# HV_Module.net
KiCad netlist of a schematic drawn in Altium Designer
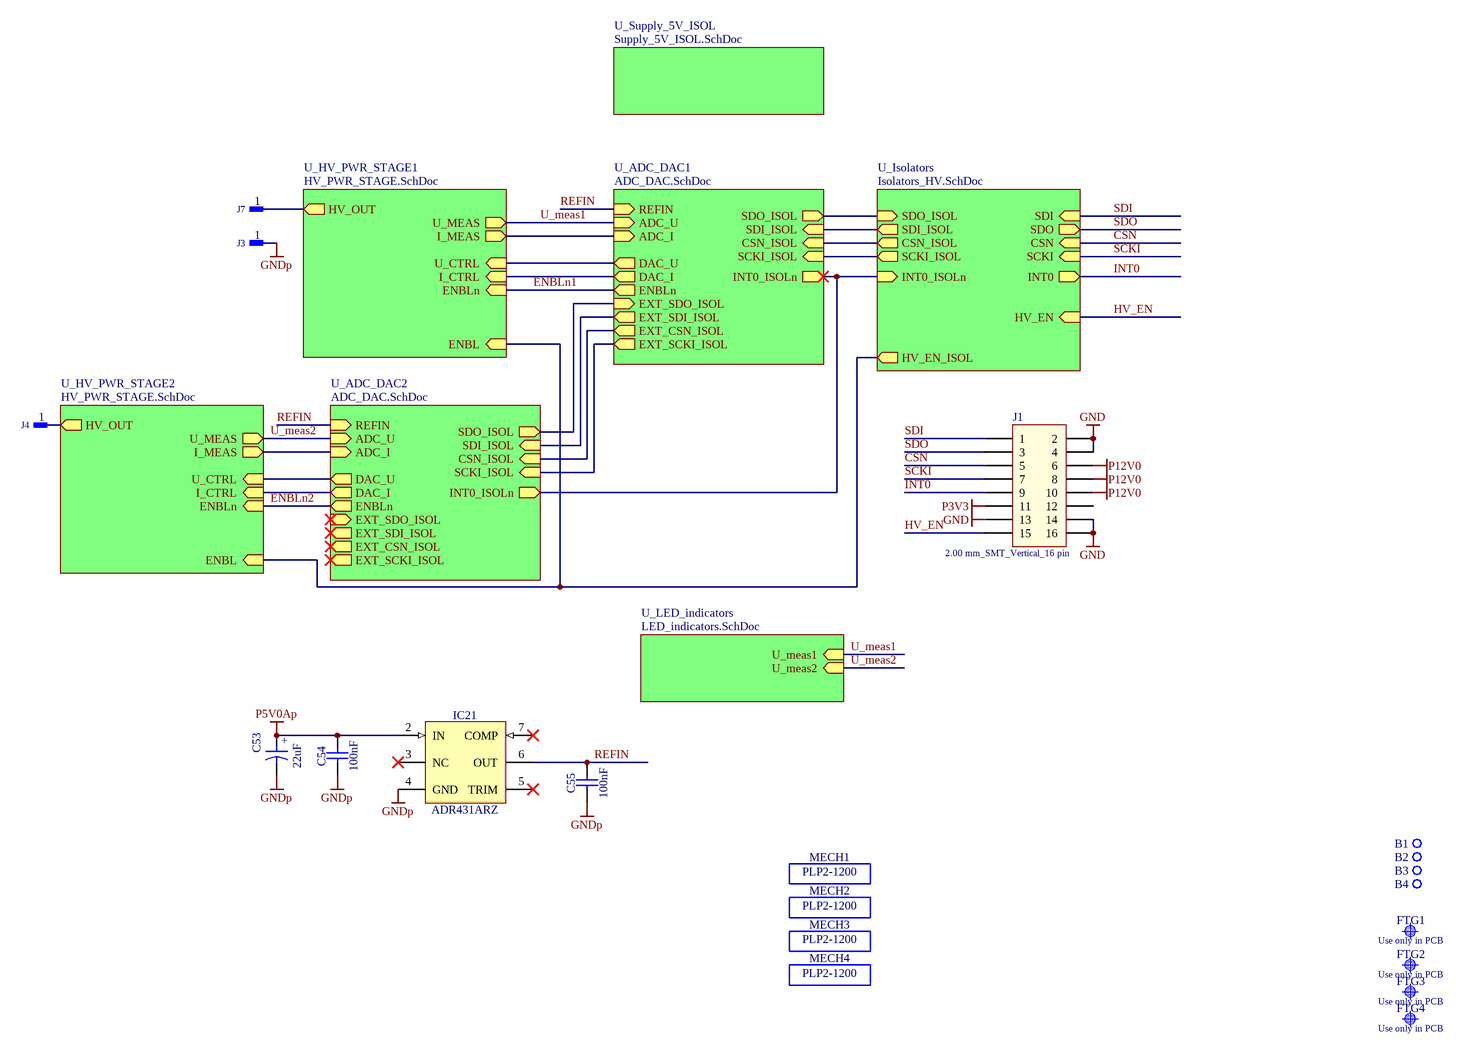
[diagram p0: HV_Module.schdoc]

(export (version "E")
  (design (tool "Eeschema 10.0.6"))
  (components
    (comp (ref "B1")
      (value "Plated Hole")
      (footprint "MTG270_500")
      (description "Single Terminal Socket")
      (fields (field (name "PART NUMBER") "PLATED_HOLE2.7_PAD5.0") (field (name "AUTHOR") "CERN DEM JMW"))
      (libsource (lib "Eletro-mechanical") (part "Single Terminal Socket"))
    )
    (comp (ref "B2")
      (value "Plated Hole")
      (footprint "MTG270_500")
      (description "Single Terminal Socket")
      (fields (field (name "PART NUMBER") "PLATED_HOLE2.7_PAD5.0") (field (name "AUTHOR") "CERN DEM JMW"))
      (libsource (lib "Eletro-mechanical") (part "Single Terminal Socket"))
    )
    (comp (ref "B3")
      (value "Plated Hole")
      (footprint "MTG270_500")
      (description "Single Terminal Socket")
      (fields (field (name "PART NUMBER") "PLATED_HOLE2.7_PAD5.0") (field (name "AUTHOR") "CERN DEM JMW"))
      (libsource (lib "Eletro-mechanical") (part "Single Terminal Socket"))
    )
    (comp (ref "B4")
      (value "Plated Hole")
      (footprint "MTG270_500")
      (description "Single Terminal Socket")
      (fields (field (name "PART NUMBER") "PLATED_HOLE2.7_PAD5.0") (field (name "AUTHOR") "CERN DEM JMW"))
      (libsource (lib "Eletro-mechanical") (part "Single Terminal Socket"))
    )
    (comp (ref "C53")
      (value "22uF")
      (footprint "CAPMP3528X210N")
      (description "Polarised capacitor")
      (fields
        (field (name "PART NUMBER") "CTE3528-21_22UF_20V_10%")
        (field (name "VOLTAGE") "20V")
        (field (name "AUTHOR") "CERN DEM JLC")
      )
      (libsource (lib "Capacitors") (part "Capacitor - polarized"))
    )
    (comp (ref "C54")
      (value "100nF")
      (footprint "CAPC1005X55N")
      (description "Non-polarised capacitor")
      (fields
        (field (name "PART NUMBER") "CC0402_100NF_16V_10%_X7R")
        (field (name "VOLTAGE") "16V")
        (field (name "AUTHOR") "CERN DEM JLC")
      )
      (libsource (lib "Capacitors") (part "Capacitor - non polarized"))
    )
    (comp (ref "C55")
      (value "100nF")
      (footprint "CAPC1005X55N")
      (description "Non-polarised capacitor")
      (fields
        (field (name "PART NUMBER") "CC0402_100NF_16V_10%_X7R")
        (field (name "VOLTAGE") "16V")
        (field (name "AUTHOR") "CERN DEM JLC")
      )
      (libsource (lib "Capacitors") (part "Capacitor - non polarized"))
    )
    (comp (ref "FTG1")
      (value "Use only in PCB")
      (footprint "FIDUCIAL_TOP_C100-200")
      (description "Fiducial Target")
      (fields (field (name "PART NUMBER") "FIDUCIAL_TARGET_C100-200") (field (name "AUTHOR") "CERN DEM JLC"))
      (libsource (lib "Eletro-mechanical") (part "Fiducial Target"))
    )
    (comp (ref "FTG2")
      (value "Use only in PCB")
      (footprint "FIDUCIAL_TOP_S100-200")
      (description "Fiducial Target")
      (fields (field (name "PART NUMBER") "FIDUCIAL_TARGET_S100-200") (field (name "AUTHOR") "CERN DEM JLC"))
      (libsource (lib "Eletro-mechanical") (part "Fiducial Target"))
    )
    (comp (ref "FTG3")
      (value "Use only in PCB")
      (footprint "FIDUCIAL_TOP_S100-200")
      (description "Fiducial Target")
      (fields (field (name "PART NUMBER") "FIDUCIAL_TARGET_S100-200") (field (name "AUTHOR") "CERN DEM JLC"))
      (libsource (lib "Eletro-mechanical") (part "Fiducial Target"))
    )
    (comp (ref "FTG4")
      (value "Use only in PCB")
      (footprint "FIDUCIAL_TOP_S100-200")
      (description "Fiducial Target")
      (fields (field (name "PART NUMBER") "FIDUCIAL_TARGET_S100-200") (field (name "AUTHOR") "CERN DEM JLC"))
      (libsource (lib "Eletro-mechanical") (part "Fiducial Target"))
    )
    (comp (ref "IC21")
      (value "ADR431ARZ")
      (footprint "SOIC127P600X175-8N")
      (fields (field (name "MANUFACTURER") "ANALOG DEVICES") (field (name "AUTHOR") "CERN DEM JLC"))
      (libsource (lib "ICs And Semiconductors") (part "ADR431"))
    )
    (comp (ref "J1")
      (value "2.00 mm_SMT_Vertical_16 pin")
      (footprint "62131621821")
      (description "Socket Header WR-PHD, Pitch 2.00 mm, SMT, Vertical, dual row, 16 pin")
      (fields (field (name "PART NUMBER") "62131621821") (field (name "PUBLISHER") "Wurth Elektronik"))
      (libsource (lib "ALTIUM-PHD_2_0_SMT_DUAL_SOCKET_HEADER_LOW_PROFILE_REEL_6213XX21821-rev18a") (part "62131621821"))
    )
    (comp (ref "J3")
      (value "SMD Pad")
      (footprint "R400X300")
      (description "Single SMD Pad")
      (fields (field (name "PART NUMBER") "SMD_PAD_4X3MM") (field (name "AUTHOR") "CERN DEM JLC"))
      (libsource (lib "Eletro-mechanical") (part "Single SMD Pad"))
    )
    (comp (ref "J4")
      (value "SMD Pad")
      (footprint "R400X300")
      (description "Single SMD Pad")
      (fields (field (name "PART NUMBER") "SMD_PAD_4X3MM") (field (name "AUTHOR") "CERN DEM JLC"))
      (libsource (lib "Eletro-mechanical") (part "Single SMD Pad"))
    )
    (comp (ref "J7")
      (value "SMD Pad")
      (footprint "R400X300")
      (description "Single SMD Pad")
      (fields (field (name "PART NUMBER") "SMD_PAD_4X3MM") (field (name "AUTHOR") "CERN DEM JLC"))
      (libsource (lib "Eletro-mechanical") (part "Single SMD Pad"))
    )
    (comp (ref "MECH1")
      (value "PLP2-1200")
      (footprint "GENERIC_MECH")
      (description "Lightguide")
      (fields (field (name "MANUFACTURER") "BIvar") (field (name "AUTHOR") "GK"))
      (libsource (lib "Mechanical") (part "Generic_mechanical"))
    )
    (comp (ref "MECH2")
      (value "PLP2-1200")
      (footprint "GENERIC_MECH")
      (description "Lightguide")
      (fields (field (name "MANUFACTURER") "BIvar") (field (name "AUTHOR") "GK"))
      (libsource (lib "Mechanical") (part "Generic_mechanical"))
    )
    (comp (ref "MECH3")
      (value "PLP2-1200")
      (footprint "GENERIC_MECH")
      (description "Lightguide")
      (fields (field (name "MANUFACTURER") "BIvar") (field (name "AUTHOR") "GK"))
      (libsource (lib "Mechanical") (part "Generic_mechanical"))
    )
    (comp (ref "MECH4")
      (value "PLP2-1200")
      (footprint "GENERIC_MECH")
      (description "Lightguide")
      (fields (field (name "MANUFACTURER") "BIvar") (field (name "AUTHOR") "GK"))
      (libsource (lib "Mechanical") (part "Generic_mechanical"))
    )
  )
  (nets
    (net (code "1") (name "/CSN") (class "Default")
      (node (ref "J1") (pin "5") (pinfunction "5_5") (pintype "passive"))
    )
    (net (code "16") (name "/HV_EN") (class "Default")
      (node (ref "J1") (pin "15") (pinfunction "15_15") (pintype "passive"))
    )
    (net (code "18") (name "/HV_OUT") (class "Default")
      (node (ref "J7") (pin "1") (pinfunction "1_1") (pintype "bidirectional"))
    )
    (net (code "19") (name "/HV_OUT_1") (class "Default")
      (node (ref "J4") (pin "1") (pinfunction "1_1") (pintype "bidirectional"))
    )
    (net (code "20") (name "/INT0") (class "Default")
      (node (ref "J1") (pin "9") (pinfunction "9_9") (pintype "passive"))
    )
    (net (code "24") (name "/REFIN") (class "Default")
      (node (ref "C55") (pin "2") (pinfunction "2_2") (pintype "passive"))
      (node (ref "IC21") (pin "6") (pinfunction "OUT_6") (pintype "power_in"))
    )
    (net (code "25") (name "/SCKI") (class "Default")
      (node (ref "J1") (pin "7") (pinfunction "7_7") (pintype "passive"))
    )
    (net (code "27") (name "/SDI") (class "Default")
      (node (ref "J1") (pin "1") (pinfunction "1_1") (pintype "passive"))
    )
    (net (code "29") (name "/SDO") (class "Default")
      (node (ref "J1") (pin "3") (pinfunction "3_3") (pintype "passive"))
    )
    (net (code "34") (name "GND") (class "Default")
      (node (ref "J1") (pin "13") (pinfunction "13_13") (pintype "passive"))
      (node (ref "J1") (pin "14") (pinfunction "14_14") (pintype "passive"))
      (node (ref "J1") (pin "16") (pinfunction "16_16") (pintype "passive"))
      (node (ref "J1") (pin "2") (pinfunction "2_2") (pintype "passive"))
      (node (ref "J1") (pin "4") (pinfunction "4_4") (pintype "passive"))
    )
    (net (code "35") (name "GNDp") (class "Default")
      (node (ref "C53") (pin "2") (pinfunction "2_2") (pintype "passive"))
      (node (ref "C54") (pin "1") (pinfunction "1_1") (pintype "passive"))
      (node (ref "C55") (pin "1") (pinfunction "1_1") (pintype "passive"))
      (node (ref "IC21") (pin "4") (pinfunction "GND_4") (pintype "power_in"))
      (node (ref "J3") (pin "1") (pinfunction "1_1") (pintype "bidirectional"))
    )
    (net (code "36") (name "P3V3") (class "Default")
      (node (ref "J1") (pin "11") (pinfunction "11_11") (pintype "passive"))
    )
    (net (code "37") (name "P5V0Ap") (class "Default")
      (node (ref "C53") (pin "1") (pinfunction "1_1") (pintype "passive"))
      (node (ref "C54") (pin "2") (pinfunction "2_2") (pintype "passive"))
      (node (ref "IC21") (pin "2") (pinfunction "IN_2") (pintype "input"))
    )
    (net (code "38") (name "P12V0") (class "Default")
      (node (ref "J1") (pin "10") (pinfunction "10_10") (pintype "passive"))
      (node (ref "J1") (pin "6") (pinfunction "6_6") (pintype "passive"))
      (node (ref "J1") (pin "8") (pinfunction "8_8") (pintype "passive"))
    )
    (net (code "39") (name "unconnected-(B1-Pad1)") (class "Default")
      (node (ref "B1") (pin "1") (pinfunction "1_1") (pintype "bidirectional"))
    )
    (net (code "40") (name "unconnected-(B2-Pad1)") (class "Default")
      (node (ref "B2") (pin "1") (pinfunction "1_1") (pintype "bidirectional"))
    )
    (net (code "41") (name "unconnected-(B3-Pad1)") (class "Default")
      (node (ref "B3") (pin "1") (pinfunction "1_1") (pintype "bidirectional"))
    )
    (net (code "42") (name "unconnected-(B4-Pad1)") (class "Default")
      (node (ref "B4") (pin "1") (pinfunction "1_1") (pintype "bidirectional"))
    )
    (net (code "43") (name "unconnected-(IC21-COMP-Pad7)") (class "Default")
      (node (ref "IC21") (pin "7") (pinfunction "COMP_7") (pintype "input+no_connect"))
    )
    (net (code "44") (name "unconnected-(IC21-NC-Pad3)") (class "Default")
      (node (ref "IC21") (pin "3") (pinfunction "NC_3") (pintype "passive+no_connect"))
    )
    (net (code "45") (name "unconnected-(IC21-TRIM-Pad5)") (class "Default")
      (node (ref "IC21") (pin "5") (pinfunction "TRIM_5") (pintype "passive+no_connect"))
    )
    (net (code "46") (name "unconnected-(J1-Pad12)") (class "Default")
      (node (ref "J1") (pin "12") (pinfunction "12_12") (pintype "passive"))
    )
  )
)
